# usb-condom.net
KiCad netlist of a schematic drawn in EAGLE
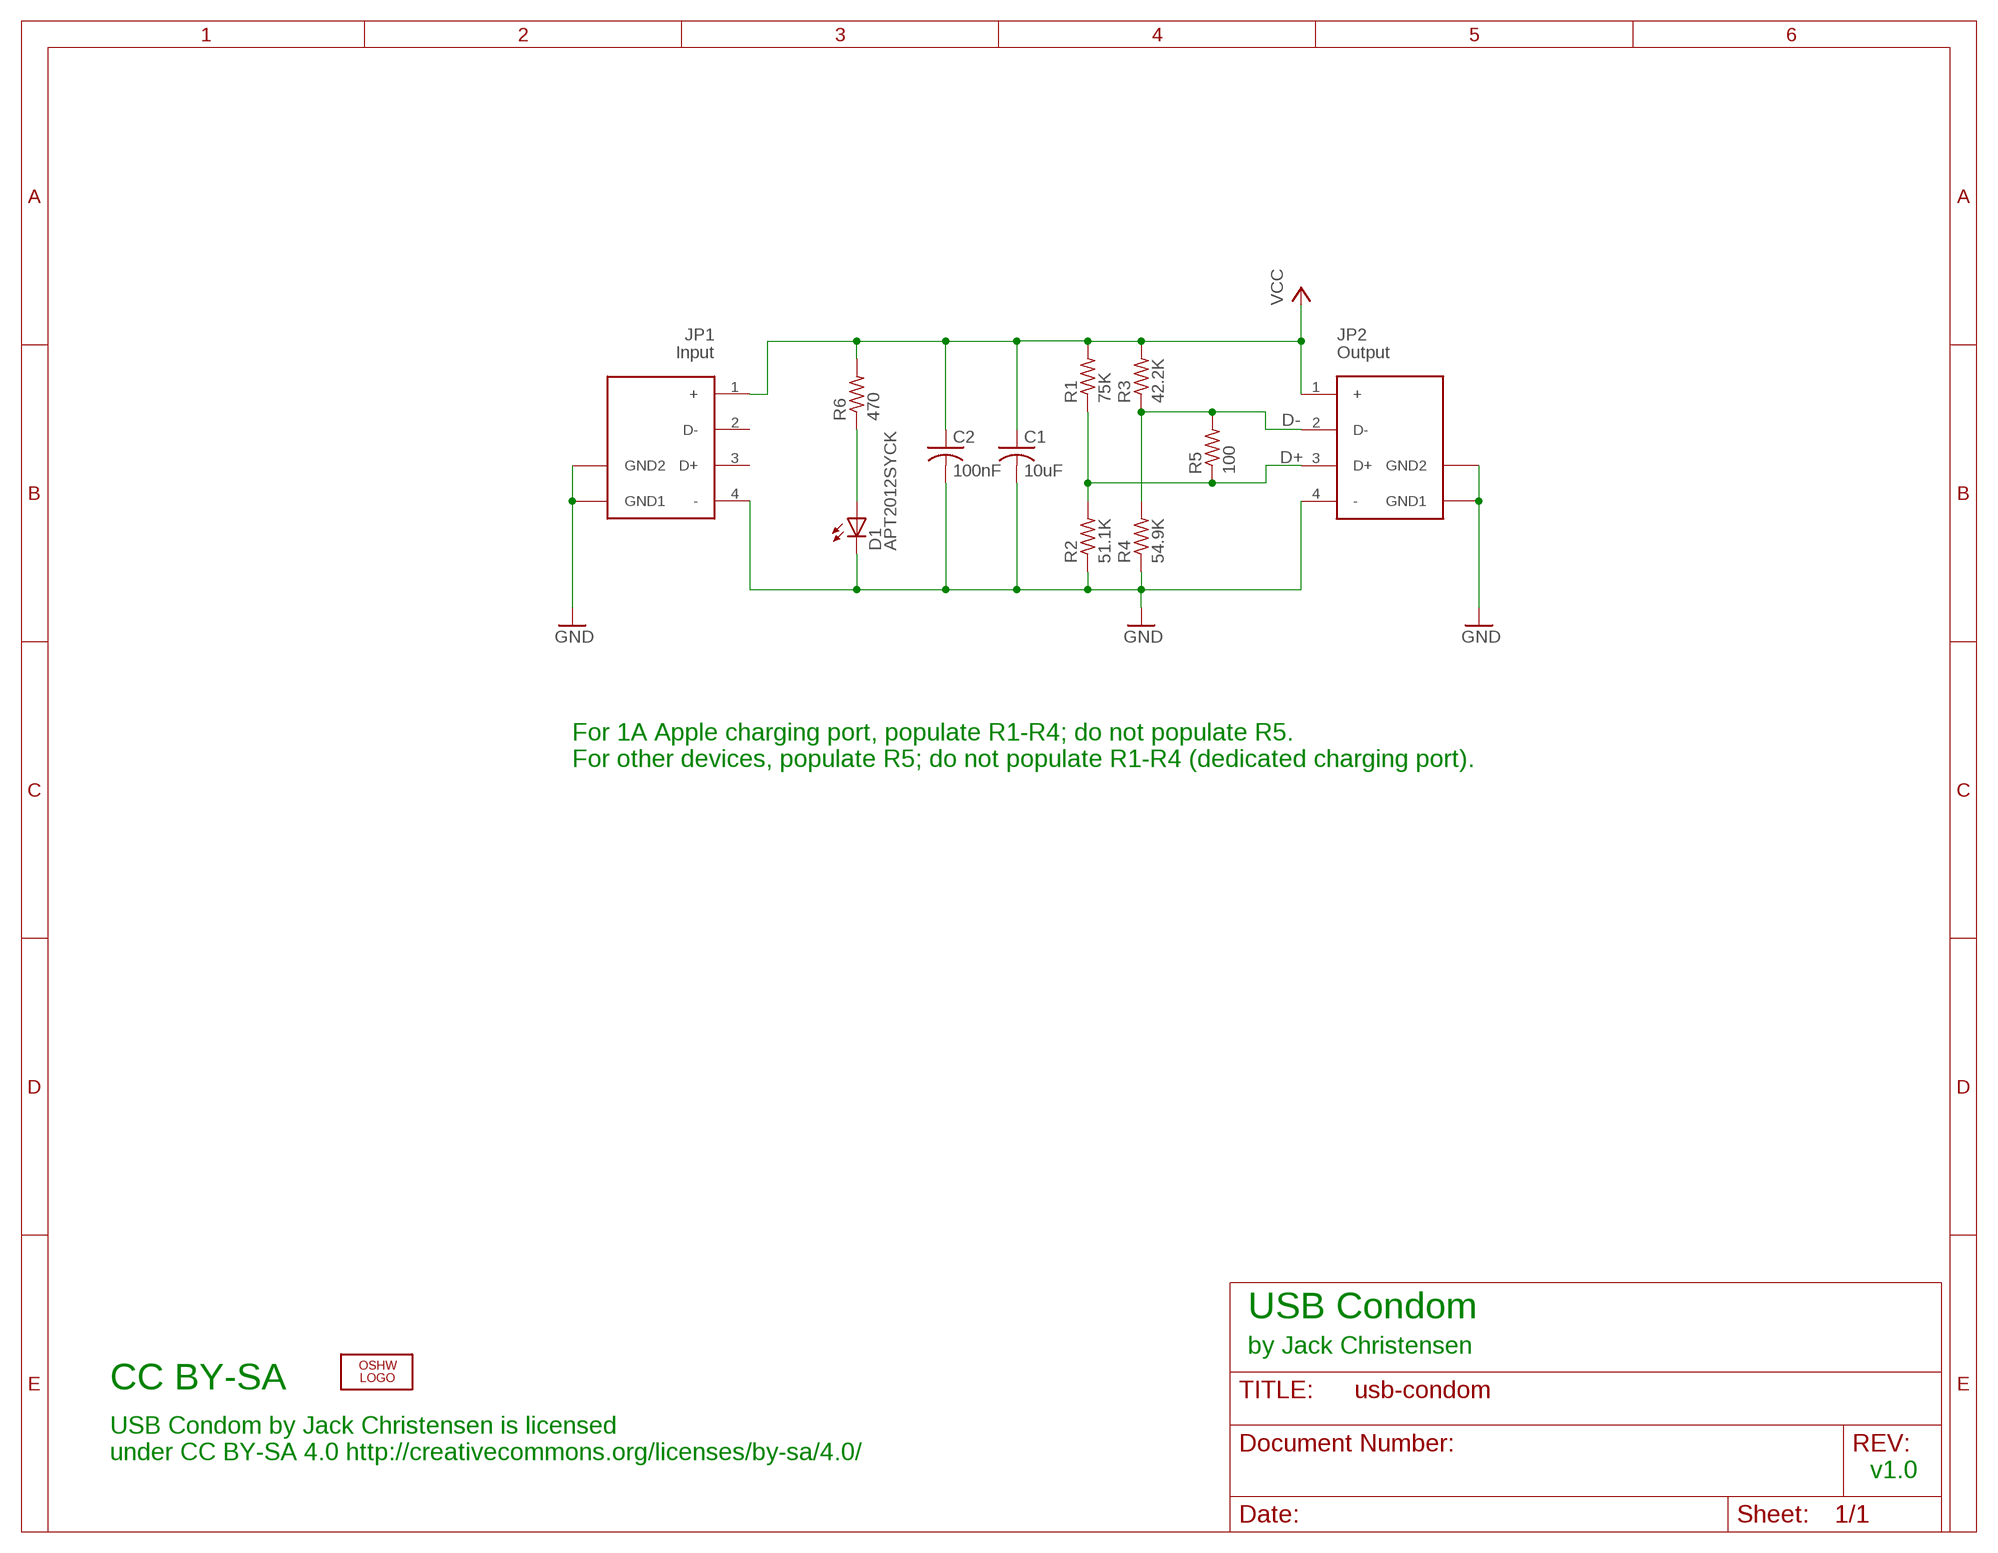
[diagram p0: schematic, sheet 1]

(export (version "E")
  (design (tool "Eeschema 10.0.6"))
  (components
    (comp (ref "C1")
      (value "10uF")
      (footprint "eagle-import:M0805")
      (libsource (lib "eagle-import") (part "C-USM0805"))
    )
    (comp (ref "C2")
      (value "100nF")
      (footprint "eagle-import:M0805")
      (libsource (lib "eagle-import") (part "C-USM0805"))
    )
    (comp (ref "D1")
      (value "APT2012SYCK")
      (footprint "eagle-import:M0805")
      (libsource (lib "eagle-import") (part "LEDM0805"))
    )
    (comp (ref "JP1")
      (value "Input")
      (footprint "eagle-import:UP2-AH-X-TH")
      (libsource (lib "eagle-import") (part "UP2-AH-TH"))
    )
    (comp (ref "JP2")
      (value "Output")
      (footprint "eagle-import:USB-A-S-RA-ADAMTECH")
      (libsource (lib "eagle-import") (part "USB-A"))
    )
    (comp (ref "LOGO1")
      (value "OSHW_LOGO_8MILX0100-NT")
      (footprint "eagle-import:OSHW_8X100_NOTEXT")
      (libsource (lib "eagle-import") (part "OSHW_LOGO_8MILX0100-NT"))
    )
    (comp (ref "R1")
      (value "75K")
      (footprint "eagle-import:M0805")
      (libsource (lib "eagle-import") (part "R-US_M0805"))
    )
    (comp (ref "R2")
      (value "51.1K")
      (footprint "eagle-import:M0805")
      (libsource (lib "eagle-import") (part "R-US_M0805"))
    )
    (comp (ref "R3")
      (value "42.2K")
      (footprint "eagle-import:M0805")
      (libsource (lib "eagle-import") (part "R-US_M0805"))
    )
    (comp (ref "R4")
      (value "54.9K")
      (footprint "eagle-import:M0805")
      (libsource (lib "eagle-import") (part "R-US_M0805"))
    )
    (comp (ref "R5")
      (value "100")
      (footprint "eagle-import:M0805")
      (libsource (lib "eagle-import") (part "R-US_M0805"))
    )
    (comp (ref "R6")
      (value "470")
      (footprint "eagle-import:M0805")
      (libsource (lib "eagle-import") (part "R-US_M0805"))
    )
  )
  (nets
    (net (code "1") (name "/D+") (class "Default")
      (node (ref "JP2") (pin "3") (pinfunction "D+_3") (pintype "bidirectional"))
      (node (ref "R1") (pin "1") (pinfunction "1_1") (pintype "passive"))
      (node (ref "R2") (pin "2") (pinfunction "2_2") (pintype "passive"))
      (node (ref "R5") (pin "1") (pinfunction "1_1") (pintype "passive"))
    )
    (net (code "2") (name "/D-") (class "Default")
      (node (ref "JP2") (pin "2") (pinfunction "D-_2") (pintype "bidirectional"))
      (node (ref "R3") (pin "1") (pinfunction "1_1") (pintype "passive"))
      (node (ref "R4") (pin "2") (pinfunction "2_2") (pintype "passive"))
      (node (ref "R5") (pin "2") (pinfunction "2_2") (pintype "passive"))
    )
    (net (code "3") (name "GND") (class "Default")
      (node (ref "C1") (pin "2") (pinfunction "2_2") (pintype "passive"))
      (node (ref "C2") (pin "2") (pinfunction "2_2") (pintype "passive"))
      (node (ref "D1") (pin "2") (pinfunction "C_2") (pintype "passive"))
      (node (ref "JP1") (pin "4") (pinfunction "-_4") (pintype "bidirectional"))
      (node (ref "JP1") (pin "P$5") (pinfunction "GND1_P$5") (pintype "bidirectional"))
      (node (ref "JP1") (pin "P$6") (pinfunction "GND2_P$6") (pintype "bidirectional"))
      (node (ref "JP2") (pin "4") (pinfunction "-_4") (pintype "bidirectional"))
      (node (ref "JP2") (pin "GND1") (pinfunction "GND1_GND1") (pintype "bidirectional"))
      (node (ref "JP2") (pin "GND2") (pinfunction "GND2_GND2") (pintype "bidirectional"))
      (node (ref "R2") (pin "1") (pinfunction "1_1") (pintype "passive"))
      (node (ref "R4") (pin "1") (pinfunction "1_1") (pintype "passive"))
    )
    (net (code "4") (name "Net-(D1-A)") (class "Default")
      (node (ref "D1") (pin "1") (pinfunction "A_1") (pintype "passive"))
      (node (ref "R6") (pin "1") (pinfunction "1_1") (pintype "passive"))
    )
    (net (code "5") (name "VCC") (class "Default")
      (node (ref "C1") (pin "1") (pinfunction "1_1") (pintype "passive"))
      (node (ref "C2") (pin "1") (pinfunction "1_1") (pintype "passive"))
      (node (ref "JP1") (pin "1") (pinfunction "+_1") (pintype "bidirectional"))
      (node (ref "JP2") (pin "1") (pinfunction "+_1") (pintype "bidirectional"))
      (node (ref "R1") (pin "2") (pinfunction "2_2") (pintype "passive"))
      (node (ref "R3") (pin "2") (pinfunction "2_2") (pintype "passive"))
      (node (ref "R6") (pin "2") (pinfunction "2_2") (pintype "passive"))
    )
    (net (code "6") (name "unconnected-(JP1-D+-Pad3)") (class "Default")
      (node (ref "JP1") (pin "3") (pinfunction "D+_3") (pintype "bidirectional"))
    )
    (net (code "7") (name "unconnected-(JP1-D--Pad2)") (class "Default")
      (node (ref "JP1") (pin "2") (pinfunction "D-_2") (pintype "bidirectional"))
    )
  )
)
